# 01-Onboard_GPS.net
KiCad netlist of a schematic drawn in Altium Designer
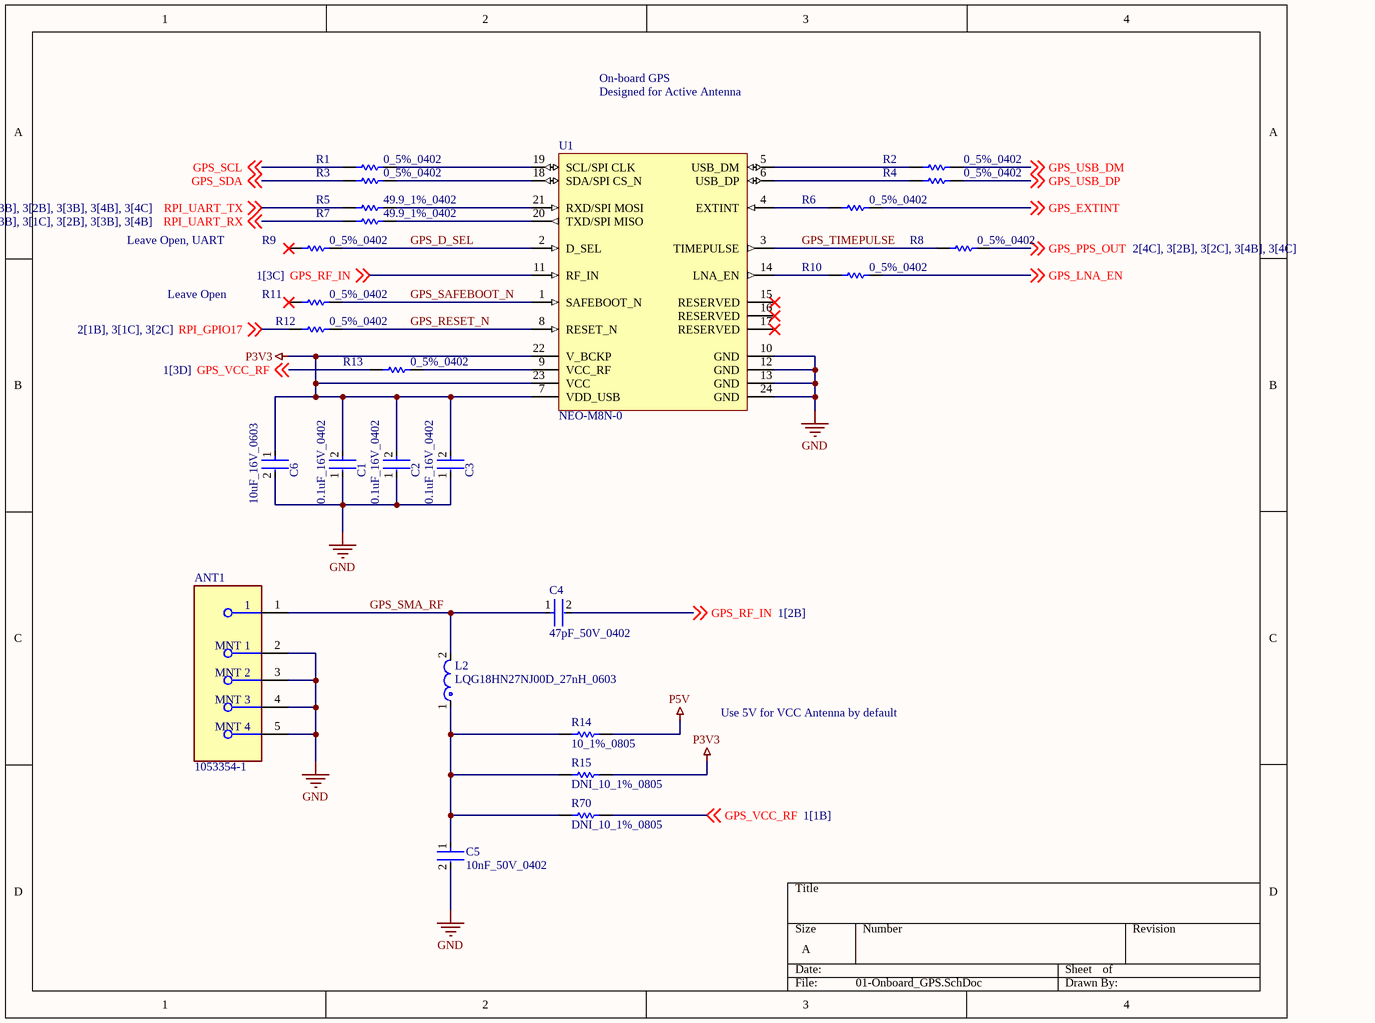
[diagram p0: 01-Onboard_GPS.SchDoc]

(export (version "E")
  (design (tool "Eeschema 10.0.6"))
  (components
    (comp (ref "ANT1")
      (value "1053354-1")
      (footprint "FP-1053354-1-MFG")
      (description "CONN SMA JACK STR 50 OHM PCB")
      (libsource (lib "Altium Content Vault") (part "c65b8a639cdaef1819ea20b5466f8fa"))
    )
    (comp (ref "C1")
      (value "0.1uF_16V_0402")
      (footprint "FP-GRM15-MFG")
      (description "CAP CER 0.1UF 16V X7R 0402")
      (fields (field (name "MANUFACTURER PART NUMBER") "GRM155R71C104KA88D") (field (name "TOLERANCE") "10%"))
      (libsource (lib "Altium Content Vault") (part "236180d848d6139a670b325ea6854c9"))
    )
    (comp (ref "C2")
      (value "0.1uF_16V_0402")
      (footprint "FP-GRM15-MFG")
      (description "CAP CER 0.1UF 16V X7R 0402")
      (fields (field (name "MANUFACTURER PART NUMBER") "GRM155R71C104KA88D") (field (name "TOLERANCE") "10%"))
      (libsource (lib "Altium Content Vault") (part "236180d848d6139a670b325ea6854c9"))
    )
    (comp (ref "C3")
      (value "0.1uF_16V_0402")
      (footprint "FP-GRM15-MFG")
      (description "CAP CER 0.1UF 16V X7R 0402")
      (fields (field (name "MANUFACTURER PART NUMBER") "GRM155R71C104KA88D") (field (name "TOLERANCE") "10%"))
      (libsource (lib "Altium Content Vault") (part "236180d848d6139a670b325ea6854c9"))
    )
    (comp (ref "C4")
      (value "47pF_50V_0402")
      (footprint "FP-C0402-BB-MFG")
      (description "CAP CER 47PF 50V C0G/NP0 0402")
      (fields (field (name "VOLTAGE") "50V") (field (name "TOLERANCE") "5%"))
      (libsource (lib "Altium Content Vault") (part "b4654b650e69147ec39a6b967a45e02"))
    )
    (comp (ref "C5")
      (value "10nF_50V_0402")
      (footprint "FP-CL165-IPC_C")
      (description "Cap Ceramic 10nF 50V X7R ±10% SMD 0402 +125°C Paper T/R")
      (fields (field (name "VOLTAGE") "50V") (field (name "TOLERANCE") "10%"))
      (libsource (lib "Altium Content Vault") (part "b4654b650e69147ec39a6b967a45e02"))
    )
    (comp (ref "C6")
      (value "10uF_16V_0603")
      (footprint "FP-0603-L_1_6_0_2-W_0_8_0-MFG")
      (description "Multilayer Ceramic Capacitor 10uF 16V X5R 20% SMD 0603 T/R")
      (fields (field (name "TOLERANCE") "20%"))
      (libsource (lib "Altium Content Vault") (part "b4654b650e69147ec39a6b967a45e02"))
    )
    (comp (ref "L2")
      (value "LQG18HN27NJ00D_27nH_0603")
      (footprint "FP-LQG18HH_00-MFG")
      (description "Multilayer type RF Inductor 27nH ±5% 0.54Ω 500mA 0603")
      (fields (field (name "TOLERANCE") "5%"))
      (libsource (lib "Altium Content Vault") (part "4cc4b267dca4c8e51f7102f422741d8"))
    )
    (comp (ref "R1")
      (value "0_5%_0402")
      (footprint "RESC1005X40X25NL05T10")
      (fields (field (name "MANUFACTURER") "Yageo / Phycomp") (field (name "PART NUMBER") "RC0402JR-070RL"))
      (libsource (lib "Altium Content Vault") (part "RES"))
    )
    (comp (ref "R2")
      (value "0_5%_0402")
      (footprint "RESC1005X40X25NL05T10")
      (fields (field (name "MANUFACTURER") "Yageo / Phycomp") (field (name "PART NUMBER") "RC0402JR-070RL"))
      (libsource (lib "Altium Content Vault") (part "RES"))
    )
    (comp (ref "R3")
      (value "0_5%_0402")
      (footprint "RESC1005X40X25NL05T10")
      (fields (field (name "MANUFACTURER") "Yageo / Phycomp") (field (name "PART NUMBER") "RC0402JR-070RL"))
      (libsource (lib "Altium Content Vault") (part "RES"))
    )
    (comp (ref "R4")
      (value "0_5%_0402")
      (footprint "RESC1005X40X25NL05T10")
      (fields (field (name "MANUFACTURER") "Yageo / Phycomp") (field (name "PART NUMBER") "RC0402JR-070RL"))
      (libsource (lib "Altium Content Vault") (part "RES"))
    )
    (comp (ref "R5")
      (value "49.9_1%_0402")
      (footprint "RESC1005X40X25LL05T05")
      (fields (field (name "PART NUMBER") "CRCW040249K9FKED") (field (name "MANUFACTURER") "Vishay Dale"))
      (libsource (lib "Altium Content Vault") (part "RES"))
    )
    (comp (ref "R6")
      (value "0_5%_0402")
      (footprint "RESC1005X40X25NL05T10")
      (fields (field (name "MANUFACTURER") "Yageo / Phycomp") (field (name "PART NUMBER") "RC0402JR-070RL"))
      (libsource (lib "Altium Content Vault") (part "RES"))
    )
    (comp (ref "R7")
      (value "49.9_1%_0402")
      (footprint "RESC1005X40X25LL05T05")
      (fields (field (name "PART NUMBER") "CRCW040249K9FKED") (field (name "MANUFACTURER") "Vishay Dale"))
      (libsource (lib "Altium Content Vault") (part "RES"))
    )
    (comp (ref "R8")
      (value "0_5%_0402")
      (footprint "RESC1005X40X25NL05T10")
      (fields (field (name "MANUFACTURER") "Yageo / Phycomp") (field (name "PART NUMBER") "RC0402JR-070RL"))
      (libsource (lib "Altium Content Vault") (part "RES"))
    )
    (comp (ref "R9")
      (value "0_5%_0402")
      (footprint "RESC1005X40X25NL05T10")
      (fields (field (name "MANUFACTURER") "Yageo / Phycomp") (field (name "PART NUMBER") "RC0402JR-070RL"))
      (libsource (lib "Altium Content Vault") (part "RES"))
    )
    (comp (ref "R10")
      (value "0_5%_0402")
      (footprint "RESC1005X40X25NL05T10")
      (fields (field (name "MANUFACTURER") "Yageo / Phycomp") (field (name "PART NUMBER") "RC0402JR-070RL"))
      (libsource (lib "Altium Content Vault") (part "RES"))
    )
    (comp (ref "R11")
      (value "0_5%_0402")
      (footprint "RESC1005X40X25NL05T10")
      (fields (field (name "MANUFACTURER") "Yageo / Phycomp") (field (name "PART NUMBER") "RC0402JR-070RL"))
      (libsource (lib "Altium Content Vault") (part "RES"))
    )
    (comp (ref "R12")
      (value "0_5%_0402")
      (footprint "RESC1005X40X25NL05T10")
      (fields (field (name "MANUFACTURER") "Yageo / Phycomp") (field (name "PART NUMBER") "RC0402JR-070RL"))
      (libsource (lib "Altium Content Vault") (part "RES"))
    )
    (comp (ref "R13")
      (value "0_5%_0402")
      (footprint "RESC1005X40X25NL05T10")
      (fields (field (name "MANUFACTURER") "Yageo / Phycomp") (field (name "PART NUMBER") "RC0402JR-070RL"))
      (libsource (lib "Altium Content Vault") (part "RES"))
    )
    (comp (ref "R14")
      (value "10_1%_0805")
      (footprint "RESC2013X60X35ML10T20")
      (description "Chip Resistor, 10 Ohm, +/- 1%, 0.125 W, -55 to 155 degC, 0805 (2012 Metric), RoHS, Tape and Reel")
      (fields (field (name "MANUFACTURER") "Yageo") (field (name "TOLERANCE") "1%"))
      (libsource (lib "Altium Content Vault") (part "RES-2"))
    )
    (comp (ref "R15")
      (value "DNI_10_1%_0805")
      (footprint "RESC2013X60X35ML10T20")
      (description "Chip Resistor, 10 Ohm, +/- 1%, 0.125 W, -55 to 155 degC, 0805 (2012 Metric), RoHS, Tape and Reel")
      (fields (field (name "MANUFACTURER") "Yageo") (field (name "TOLERANCE") "1%"))
      (libsource (lib "Altium Content Vault") (part "RES-2"))
    )
    (comp (ref "R70")
      (value "DNI_10_1%_0805")
      (footprint "RESC2013X60X35ML10T20")
      (description "Chip Resistor, 10 Ohm, +/- 1%, 0.125 W, -55 to 155 degC, 0805 (2012 Metric), RoHS, Tape and Reel")
      (fields (field (name "MANUFACTURER") "Yageo") (field (name "TOLERANCE") "1%"))
      (libsource (lib "Altium Content Vault") (part "RES-2"))
    )
    (comp (ref "U1")
      (value "NEO-M8N-0")
      (footprint "UBX-NEO-M8-24_V")
      (description "U-Blox M8 Concurrent Gnss Module, 3.6 V, -40 to 85 degC, 24-Pin SMD, RoHS, Tape and Reel")
      (fields (field (name "MANUFACTURER") "U-Blox"))
      (libsource (lib "Altium Content Vault") (part "UBX-NEO-M8X-24"))
    )
  )
  (nets
    (net (code "1") (name "/GPS_D_SEL") (class "Default")
      (node (ref "R9") (pin "2") (pinfunction "2_2") (pintype "passive"))
      (node (ref "U1") (pin "2") (pinfunction "D_SEL_2") (pintype "input"))
    )
    (net (code "2") (name "/GPS_RESET_N") (class "Default")
      (node (ref "R12") (pin "2") (pinfunction "2_2") (pintype "passive"))
      (node (ref "U1") (pin "8") (pinfunction "RESET_N_8") (pintype "input"))
    )
    (net (code "3") (name "/GPS_SAFEBOOT_N") (class "Default")
      (node (ref "R11") (pin "2") (pinfunction "2_2") (pintype "passive"))
      (node (ref "U1") (pin "1") (pinfunction "SAFEBOOT_N_1") (pintype "input"))
    )
    (net (code "4") (name "/GPS_SMA_RF") (class "Default")
      (node (ref "ANT1") (pin "1") (pinfunction "1_1") (pintype "passive"))
      (node (ref "C4") (pin "1") (pinfunction "1_1") (pintype "passive"))
      (node (ref "L2") (pin "2") (pinfunction "2_2") (pintype "passive"))
    )
    (net (code "5") (name "/GPS_TIMEPULSE") (class "Default")
      (node (ref "R8") (pin "1") (pinfunction "1_1") (pintype "passive"))
      (node (ref "U1") (pin "3") (pinfunction "TIMEPULSE_3") (pintype "output"))
    )
    (net (code "6") (name "GND") (class "Default")
      (node (ref "ANT1") (pin "2") (pinfunction "MNT_1_2") (pintype "passive"))
      (node (ref "ANT1") (pin "3") (pinfunction "MNT_2_3") (pintype "passive"))
      (node (ref "ANT1") (pin "4") (pinfunction "MNT_3_4") (pintype "passive"))
      (node (ref "ANT1") (pin "5") (pinfunction "MNT_4_5") (pintype "passive"))
      (node (ref "C1") (pin "1") (pinfunction "1_1") (pintype "passive"))
      (node (ref "C2") (pin "1") (pinfunction "1_1") (pintype "passive"))
      (node (ref "C3") (pin "1") (pinfunction "1_1") (pintype "passive"))
      (node (ref "C5") (pin "2") (pinfunction "2_2") (pintype "passive"))
      (node (ref "C6") (pin "2") (pinfunction "2_2") (pintype "passive"))
      (node (ref "U1") (pin "10") (pinfunction "GND_10") (pintype "power_in"))
      (node (ref "U1") (pin "12") (pinfunction "GND_12") (pintype "power_in"))
      (node (ref "U1") (pin "13") (pinfunction "GND_13") (pintype "power_in"))
      (node (ref "U1") (pin "24") (pinfunction "GND_24") (pintype "power_in"))
    )
    (net (code "7") (name "GPS_EXTINT") (class "Default")
      (node (ref "R6") (pin "2") (pinfunction "2_2") (pintype "passive"))
    )
    (net (code "8") (name "GPS_LNA_EN") (class "Default")
      (node (ref "R10") (pin "2") (pinfunction "2_2") (pintype "passive"))
    )
    (net (code "9") (name "GPS_PPS_OUT") (class "Default")
      (node (ref "R8") (pin "2") (pinfunction "2_2") (pintype "passive"))
    )
    (net (code "10") (name "GPS_RF_IN") (class "Default")
      (node (ref "C4") (pin "2") (pinfunction "2_2") (pintype "passive"))
      (node (ref "U1") (pin "11") (pinfunction "RF_IN_11") (pintype "input"))
    )
    (net (code "11") (name "GPS_SCL") (class "Default")
      (node (ref "R1") (pin "1") (pinfunction "1_1") (pintype "passive"))
    )
    (net (code "12") (name "GPS_SDA") (class "Default")
      (node (ref "R3") (pin "1") (pinfunction "1_1") (pintype "passive"))
    )
    (net (code "13") (name "GPS_USB_DM") (class "Default")
      (node (ref "R2") (pin "1") (pinfunction "1_1") (pintype "passive"))
    )
    (net (code "14") (name "GPS_USB_DP") (class "Default")
      (node (ref "R4") (pin "1") (pinfunction "1_1") (pintype "passive"))
    )
    (net (code "15") (name "GPS_VCC_RF") (class "Default")
      (node (ref "R13") (pin "1") (pinfunction "1_1") (pintype "passive"))
      (node (ref "R70") (pin "2") (pinfunction "2_2") (pintype "passive"))
    )
    (net (code "16") (name "Net-(C5-Pad1)") (class "Default")
      (node (ref "C5") (pin "1") (pinfunction "1_1") (pintype "passive"))
      (node (ref "L2") (pin "1") (pinfunction "1_1") (pintype "passive"))
      (node (ref "R14") (pin "1") (pinfunction "1_1") (pintype "passive"))
      (node (ref "R15") (pin "1") (pinfunction "1_1") (pintype "passive"))
      (node (ref "R70") (pin "1") (pinfunction "1_1") (pintype "passive"))
    )
    (net (code "17") (name "Net-(U1-EXTINT)") (class "Default")
      (node (ref "R6") (pin "1") (pinfunction "1_1") (pintype "passive"))
      (node (ref "U1") (pin "4") (pinfunction "EXTINT_4") (pintype "input"))
    )
    (net (code "18") (name "Net-(U1-LNA_EN)") (class "Default")
      (node (ref "R10") (pin "1") (pinfunction "1_1") (pintype "passive"))
      (node (ref "U1") (pin "14") (pinfunction "LNA_EN_14") (pintype "output"))
    )
    (net (code "19") (name "Net-(U1-RXD{slash}SPI_MOSI)") (class "Default")
      (node (ref "R5") (pin "2") (pinfunction "2_2") (pintype "passive"))
      (node (ref "U1") (pin "21") (pinfunction "RXD/SPI_MOSI_21") (pintype "input"))
    )
    (net (code "20") (name "Net-(U1-SCL{slash}SPI_CLK)") (class "Default")
      (node (ref "R1") (pin "2") (pinfunction "2_2") (pintype "passive"))
      (node (ref "U1") (pin "19") (pinfunction "SCL/SPI_CLK_19") (pintype "bidirectional"))
    )
    (net (code "21") (name "Net-(U1-SDA{slash}SPI_CS_N)") (class "Default")
      (node (ref "R3") (pin "2") (pinfunction "2_2") (pintype "passive"))
      (node (ref "U1") (pin "18") (pinfunction "SDA/SPI_CS_N_18") (pintype "bidirectional"))
    )
    (net (code "22") (name "Net-(U1-TXD{slash}SPI_MISO)") (class "Default")
      (node (ref "R7") (pin "2") (pinfunction "2_2") (pintype "passive"))
      (node (ref "U1") (pin "20") (pinfunction "TXD/SPI_MISO_20") (pintype "output"))
    )
    (net (code "23") (name "Net-(U1-USB_DM)") (class "Default")
      (node (ref "R2") (pin "2") (pinfunction "2_2") (pintype "passive"))
      (node (ref "U1") (pin "5") (pinfunction "USB_DM_5") (pintype "bidirectional"))
    )
    (net (code "24") (name "Net-(U1-USB_DP)") (class "Default")
      (node (ref "R4") (pin "2") (pinfunction "2_2") (pintype "passive"))
      (node (ref "U1") (pin "6") (pinfunction "USB_DP_6") (pintype "bidirectional"))
    )
    (net (code "25") (name "Net-(U1-VCC_RF)") (class "Default")
      (node (ref "R13") (pin "2") (pinfunction "2_2") (pintype "passive"))
      (node (ref "U1") (pin "9") (pinfunction "VCC_RF_9") (pintype "power_in"))
    )
    (net (code "26") (name "P3V3") (class "Default")
      (node (ref "C1") (pin "2") (pinfunction "2_2") (pintype "passive"))
      (node (ref "C2") (pin "2") (pinfunction "2_2") (pintype "passive"))
      (node (ref "C3") (pin "2") (pinfunction "2_2") (pintype "passive"))
      (node (ref "C6") (pin "1") (pinfunction "1_1") (pintype "passive"))
      (node (ref "R15") (pin "2") (pinfunction "2_2") (pintype "passive"))
      (node (ref "U1") (pin "22") (pinfunction "V_BCKP_22") (pintype "power_in"))
      (node (ref "U1") (pin "23") (pinfunction "VCC_23") (pintype "power_in"))
      (node (ref "U1") (pin "7") (pinfunction "VDD_USB_7") (pintype "power_in"))
    )
    (net (code "27") (name "P5V") (class "Default")
      (node (ref "R14") (pin "2") (pinfunction "2_2") (pintype "passive"))
    )
    (net (code "28") (name "RPI_GPIO17") (class "Default")
      (node (ref "R12") (pin "1") (pinfunction "1_1") (pintype "passive"))
    )
    (net (code "29") (name "RPI_UART_RX") (class "Default")
      (node (ref "R7") (pin "1") (pinfunction "1_1") (pintype "passive"))
    )
    (net (code "30") (name "RPI_UART_TX") (class "Default")
      (node (ref "R5") (pin "1") (pinfunction "1_1") (pintype "passive"))
    )
    (net (code "31") (name "unconnected-(R9-Pad1)") (class "Default")
      (node (ref "R9") (pin "1") (pinfunction "1_1") (pintype "passive+no_connect"))
    )
    (net (code "32") (name "unconnected-(R11-Pad1)") (class "Default")
      (node (ref "R11") (pin "1") (pinfunction "1_1") (pintype "passive+no_connect"))
    )
    (net (code "33") (name "unconnected-(U1-RESERVED-Pad15)") (class "Default")
      (node (ref "U1") (pin "15") (pinfunction "RESERVED_15") (pintype "passive+no_connect"))
    )
    (net (code "34") (name "unconnected-(U1-RESERVED-Pad16)") (class "Default")
      (node (ref "U1") (pin "16") (pinfunction "RESERVED_16") (pintype "passive+no_connect"))
    )
    (net (code "35") (name "unconnected-(U1-RESERVED-Pad17)") (class "Default")
      (node (ref "U1") (pin "17") (pinfunction "RESERVED_17") (pintype "passive+no_connect"))
    )
  )
)
